# 2_-_ports.net
KiCad netlist of a schematic drawn in Altium Designer
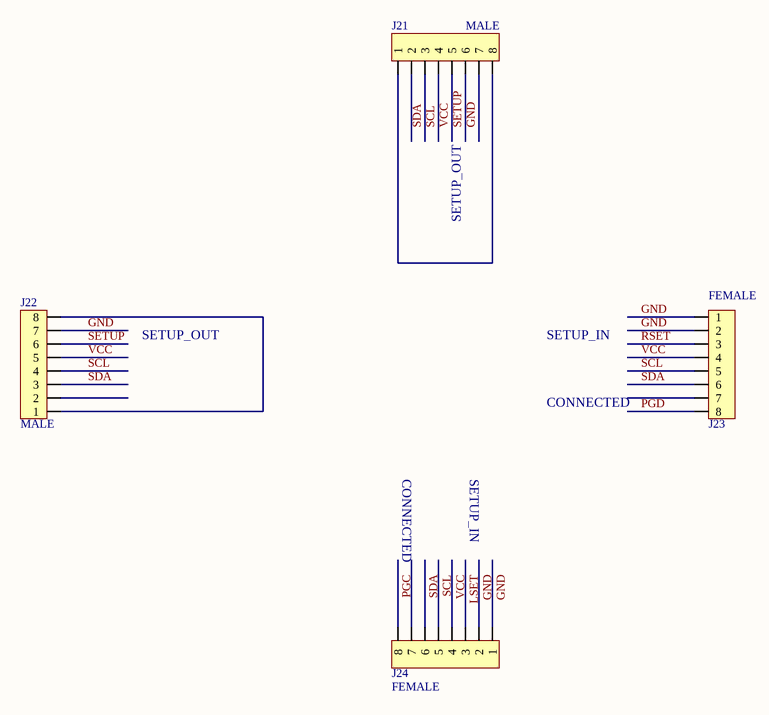
[diagram p0: 2 - ports.SchDoc]

(export (version "E")
  (design (tool "Eeschema 10.0.6"))
  (components
    (comp (ref "J21")
      (value "MALE")
      (footprint "Jarrett:HDR1X8_2.54_180H")
      (description "Header")
      (libsource (lib "") (part "HDR1x8_2.54_1"))
    )
    (comp (ref "J22")
      (value "MALE")
      (footprint "Jarrett:HDR1X8_2.54_180H")
      (description "Header")
      (libsource (lib "Jarrett") (part "HDR1x8_2.54"))
    )
    (comp (ref "J23")
      (value "FEMALE")
      (footprint "Jarrett:HDR1X8_2.54_180H")
      (description "Header")
      (libsource (lib "") (part "HDR1x8_2.54_3"))
    )
    (comp (ref "J24")
      (value "FEMALE")
      (footprint "Jarrett:HDR1X8_2.54_180H")
      (description "Header")
      (libsource (lib "") (part "HDR1x8_2.54_2"))
    )
  )
  (nets
    (net (code "1") (name "/GND") (class "Default")
      (node (ref "J21") (pin "7") (pinfunction "7_7") (pintype "passive"))
      (node (ref "J22") (pin "7") (pinfunction "7_7") (pintype "passive"))
      (node (ref "J23") (pin "1") (pinfunction "1_1") (pintype "passive"))
      (node (ref "J23") (pin "2") (pinfunction "2_2") (pintype "passive"))
      (node (ref "J24") (pin "1") (pinfunction "1_1") (pintype "passive"))
      (node (ref "J24") (pin "2") (pinfunction "2_2") (pintype "passive"))
    )
    (net (code "2") (name "/LSET") (class "Default")
      (node (ref "J24") (pin "3") (pinfunction "3_3") (pintype "passive"))
    )
    (net (code "3") (name "/PGC") (class "Default")
      (node (ref "J24") (pin "8") (pinfunction "8_8") (pintype "passive"))
    )
    (net (code "4") (name "/PGD") (class "Default")
      (node (ref "J23") (pin "8") (pinfunction "8_8") (pintype "passive"))
    )
    (net (code "5") (name "/RSET") (class "Default")
      (node (ref "J23") (pin "3") (pinfunction "3_3") (pintype "passive"))
    )
    (net (code "6") (name "/SCL") (class "Default")
      (node (ref "J21") (pin "4") (pinfunction "4_4") (pintype "passive"))
      (node (ref "J22") (pin "4") (pinfunction "4_4") (pintype "passive"))
      (node (ref "J23") (pin "5") (pinfunction "5_5") (pintype "passive"))
      (node (ref "J24") (pin "5") (pinfunction "5_5") (pintype "passive"))
    )
    (net (code "7") (name "/SDA") (class "Default")
      (node (ref "J21") (pin "3") (pinfunction "3_3") (pintype "passive"))
      (node (ref "J22") (pin "3") (pinfunction "3_3") (pintype "passive"))
      (node (ref "J23") (pin "6") (pinfunction "6_6") (pintype "passive"))
      (node (ref "J24") (pin "6") (pinfunction "6_6") (pintype "passive"))
    )
    (net (code "8") (name "/SETUP") (class "Default")
      (node (ref "J21") (pin "6") (pinfunction "6_6") (pintype "passive"))
      (node (ref "J22") (pin "6") (pinfunction "6_6") (pintype "passive"))
    )
    (net (code "9") (name "/VCC") (class "Default")
      (node (ref "J21") (pin "5") (pinfunction "5_5") (pintype "passive"))
      (node (ref "J22") (pin "5") (pinfunction "5_5") (pintype "passive"))
      (node (ref "J23") (pin "4") (pinfunction "4_4") (pintype "passive"))
      (node (ref "J24") (pin "4") (pinfunction "4_4") (pintype "passive"))
    )
    (net (code "10") (name "Net-(J21-Pad1)") (class "Default")
      (node (ref "J21") (pin "1") (pinfunction "1_1") (pintype "passive"))
      (node (ref "J21") (pin "8") (pinfunction "8_8") (pintype "passive"))
    )
    (net (code "11") (name "Net-(J22-Pad1)") (class "Default")
      (node (ref "J22") (pin "1") (pinfunction "1_1") (pintype "passive"))
      (node (ref "J22") (pin "8") (pinfunction "8_8") (pintype "passive"))
    )
    (net (code "12") (name "unconnected-(J21-Pad2)") (class "Default")
      (node (ref "J21") (pin "2") (pinfunction "2_2") (pintype "passive"))
    )
    (net (code "13") (name "unconnected-(J22-Pad2)") (class "Default")
      (node (ref "J22") (pin "2") (pinfunction "2_2") (pintype "passive"))
    )
    (net (code "14") (name "unconnected-(J23-Pad7)") (class "Default")
      (node (ref "J23") (pin "7") (pinfunction "7_7") (pintype "passive"))
    )
    (net (code "15") (name "unconnected-(J24-Pad7)") (class "Default")
      (node (ref "J24") (pin "7") (pinfunction "7_7") (pintype "passive"))
    )
  )
)
